# Sensor.net
KiCad netlist of a schematic drawn in Altium Designer
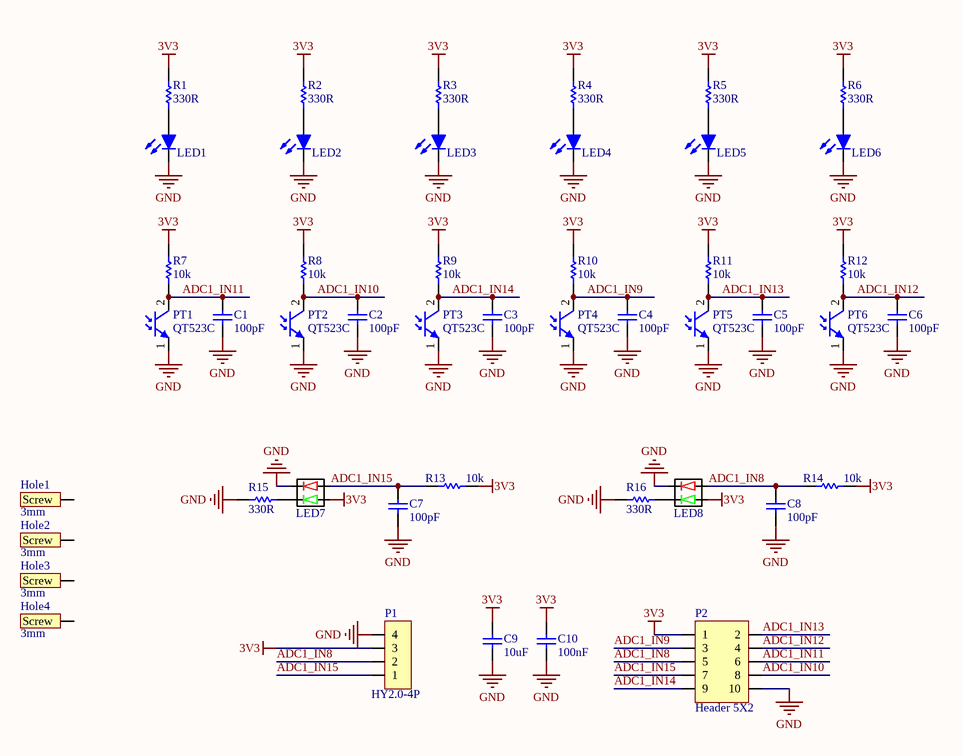
[diagram p0: Sensor.SchDoc]

(export (version "E")
  (design (tool "Eeschema 10.0.6"))
  (components
    (comp (ref "C1")
      (value "100pF")
      (footprint "C 0603 (1608)")
      (description "Capacitor non-pol")
      (libsource (lib "BKIT4U_LIB") (part "Capacitor NP"))
    )
    (comp (ref "C2")
      (value "100pF")
      (footprint "C 0603 (1608)")
      (description "Capacitor non-pol")
      (libsource (lib "BKIT4U_LIB") (part "Capacitor NP"))
    )
    (comp (ref "C3")
      (value "100pF")
      (footprint "C 0603 (1608)")
      (description "Capacitor non-pol")
      (libsource (lib "BKIT4U_LIB") (part "Capacitor NP"))
    )
    (comp (ref "C4")
      (value "100pF")
      (footprint "C 0603 (1608)")
      (description "Capacitor non-pol")
      (libsource (lib "BKIT4U_LIB") (part "Capacitor NP"))
    )
    (comp (ref "C5")
      (value "100pF")
      (footprint "C 0603 (1608)")
      (description "Capacitor non-pol")
      (libsource (lib "BKIT4U_LIB") (part "Capacitor NP"))
    )
    (comp (ref "C6")
      (value "100pF")
      (footprint "C 0603 (1608)")
      (description "Capacitor non-pol")
      (libsource (lib "BKIT4U_LIB") (part "Capacitor NP"))
    )
    (comp (ref "C7")
      (value "100pF")
      (footprint "C 0603 (1608)")
      (description "Capacitor non-pol")
      (libsource (lib "BKIT4U_LIB") (part "Capacitor NP"))
    )
    (comp (ref "C8")
      (value "100pF")
      (footprint "C 0603 (1608)")
      (description "Capacitor non-pol")
      (libsource (lib "BKIT4U_LIB") (part "Capacitor NP"))
    )
    (comp (ref "C9")
      (value "10uF")
      (footprint "C 0603 (1608)")
      (description "Capacitor non-pol")
      (libsource (lib "BKIT4U_LIB") (part "Capacitor NP"))
    )
    (comp (ref "C10")
      (value "100nF")
      (footprint "C 0603 (1608)")
      (description "Capacitor non-pol")
      (libsource (lib "BKIT4U_LIB") (part "Capacitor NP"))
    )
    (comp (ref "Hole1") (value "3mm") (footprint "SCREW/3M/7M") (libsource (lib "BKIT4U_LIB") (part "Screw")))
    (comp (ref "Hole2") (value "3mm") (footprint "SCREW/3M/7M") (libsource (lib "BKIT4U_LIB") (part "Screw")))
    (comp (ref "Hole3") (value "3mm") (footprint "SCREW/3M/7M") (libsource (lib "BKIT4U_LIB") (part "Screw")))
    (comp (ref "Hole4") (value "3mm") (footprint "SCREW/3M/7M") (libsource (lib "BKIT4U_LIB") (part "Screw")))
    (comp (ref "LED1")
      (value "Led-Red")
      (footprint "LED 5MM")
      (description "Typical LED")
      (libsource (lib "BKIT4U_LIB") (part "Led"))
    )
    (comp (ref "LED2")
      (value "Led-Red")
      (footprint "LED 5MM")
      (description "Typical LED")
      (libsource (lib "BKIT4U_LIB") (part "Led"))
    )
    (comp (ref "LED3")
      (value "Led-Red")
      (footprint "LED 5MM")
      (description "Typical LED")
      (libsource (lib "BKIT4U_LIB") (part "Led"))
    )
    (comp (ref "LED4")
      (value "Led-Red")
      (footprint "LED 5MM")
      (description "Typical LED")
      (libsource (lib "BKIT4U_LIB") (part "Led"))
    )
    (comp (ref "LED5")
      (value "Led-Red")
      (footprint "LED 5MM")
      (description "Typical LED")
      (libsource (lib "BKIT4U_LIB") (part "Led"))
    )
    (comp (ref "LED6")
      (value "Led-Red")
      (footprint "LED 5MM")
      (description "Typical LED")
      (libsource (lib "BKIT4U_LIB") (part "Led"))
    )
    (comp (ref "LED7")
      (value "LED F2/3MM 90")
      (footprint "LED 2x3MM 90")
      (description "Typical LED")
      (libsource (lib "BKIT4U_LIB") (part "LED F2/3MM 90"))
    )
    (comp (ref "LED8")
      (value "LED F2/3MM 90")
      (footprint "LED 2x3MM 90")
      (description "Typical LED")
      (libsource (lib "BKIT4U_LIB") (part "LED F2/3MM 90"))
    )
    (comp (ref "P1")
      (value "HY2.0-4P")
      (footprint "HY2.0-4P-RA")
      (description "Header, 4-Pin")
      (libsource (lib "BKIT4U_LIB") (part "Header 4"))
    )
    (comp (ref "P2")
      (value "Header 5X2")
      (footprint "DC3-10P-1.27MM")
      (description "Header, 5-Pin, Dual row")
      (fields (field (name "PUBLISHER") "Altium Limited"))
      (libsource (lib "BKIT4U_LIB") (part "Header 5X2"))
    )
    (comp (ref "PT1")
      (value "QT523C")
      (footprint "QT523C 5800B")
      (description "PHOTODIODE 5800B")
      (libsource (lib "BKIT4U_LIB") (part "QT523C"))
    )
    (comp (ref "PT2")
      (value "QT523C")
      (footprint "QT523C 5800B")
      (description "PHOTODIODE 5800B")
      (libsource (lib "BKIT4U_LIB") (part "QT523C"))
    )
    (comp (ref "PT3")
      (value "QT523C")
      (footprint "QT523C 5800B")
      (description "PHOTODIODE 5800B")
      (libsource (lib "BKIT4U_LIB") (part "QT523C"))
    )
    (comp (ref "PT4")
      (value "QT523C")
      (footprint "QT523C 5800B")
      (description "PHOTODIODE 5800B")
      (libsource (lib "BKIT4U_LIB") (part "QT523C"))
    )
    (comp (ref "PT5")
      (value "QT523C")
      (footprint "QT523C 5800B")
      (description "PHOTODIODE 5800B")
      (libsource (lib "BKIT4U_LIB") (part "QT523C"))
    )
    (comp (ref "PT6")
      (value "QT523C")
      (footprint "QT523C 5800B")
      (description "PHOTODIODE 5800B")
      (libsource (lib "BKIT4U_LIB") (part "QT523C"))
    )
    (comp (ref "R1")
      (value "330R")
      (footprint "R 0603 (1608)")
      (description "Resistor")
      (fields (field (name "PUBLISHER") "Altium Limited"))
      (libsource (lib "BKIT4U_LIB") (part "Resistor"))
    )
    (comp (ref "R2")
      (value "330R")
      (footprint "R 0603 (1608)")
      (description "Resistor")
      (fields (field (name "PUBLISHER") "Altium Limited"))
      (libsource (lib "BKIT4U_LIB") (part "Resistor"))
    )
    (comp (ref "R3")
      (value "330R")
      (footprint "R 0603 (1608)")
      (description "Resistor")
      (fields (field (name "PUBLISHER") "Altium Limited"))
      (libsource (lib "BKIT4U_LIB") (part "Resistor"))
    )
    (comp (ref "R4")
      (value "330R")
      (footprint "R 0603 (1608)")
      (description "Resistor")
      (fields (field (name "PUBLISHER") "Altium Limited"))
      (libsource (lib "BKIT4U_LIB") (part "Resistor"))
    )
    (comp (ref "R5")
      (value "330R")
      (footprint "R 0603 (1608)")
      (description "Resistor")
      (fields (field (name "PUBLISHER") "Altium Limited"))
      (libsource (lib "BKIT4U_LIB") (part "Resistor"))
    )
    (comp (ref "R6")
      (value "330R")
      (footprint "R 0603 (1608)")
      (description "Resistor")
      (fields (field (name "PUBLISHER") "Altium Limited"))
      (libsource (lib "BKIT4U_LIB") (part "Resistor"))
    )
    (comp (ref "R7")
      (value "10k")
      (footprint "R 0603 (1608)")
      (description "Resistor")
      (fields (field (name "PUBLISHER") "Altium Limited"))
      (libsource (lib "BKIT4U_LIB") (part "Resistor"))
    )
    (comp (ref "R8")
      (value "10k")
      (footprint "R 0603 (1608)")
      (description "Resistor")
      (fields (field (name "PUBLISHER") "Altium Limited"))
      (libsource (lib "BKIT4U_LIB") (part "Resistor"))
    )
    (comp (ref "R9")
      (value "10k")
      (footprint "R 0603 (1608)")
      (description "Resistor")
      (fields (field (name "PUBLISHER") "Altium Limited"))
      (libsource (lib "BKIT4U_LIB") (part "Resistor"))
    )
    (comp (ref "R10")
      (value "10k")
      (footprint "R 0603 (1608)")
      (description "Resistor")
      (fields (field (name "PUBLISHER") "Altium Limited"))
      (libsource (lib "BKIT4U_LIB") (part "Resistor"))
    )
    (comp (ref "R11")
      (value "10k")
      (footprint "R 0603 (1608)")
      (description "Resistor")
      (fields (field (name "PUBLISHER") "Altium Limited"))
      (libsource (lib "BKIT4U_LIB") (part "Resistor"))
    )
    (comp (ref "R12")
      (value "10k")
      (footprint "R 0603 (1608)")
      (description "Resistor")
      (fields (field (name "PUBLISHER") "Altium Limited"))
      (libsource (lib "BKIT4U_LIB") (part "Resistor"))
    )
    (comp (ref "R13")
      (value "10k")
      (footprint "R 0603 (1608)")
      (description "Resistor")
      (fields (field (name "PUBLISHER") "Altium Limited"))
      (libsource (lib "BKIT4U_LIB") (part "Resistor"))
    )
    (comp (ref "R14")
      (value "10k")
      (footprint "R 0603 (1608)")
      (description "Resistor")
      (fields (field (name "PUBLISHER") "Altium Limited"))
      (libsource (lib "BKIT4U_LIB") (part "Resistor"))
    )
    (comp (ref "R15")
      (value "330R")
      (footprint "R 0603 (1608)")
      (description "Resistor")
      (fields (field (name "PUBLISHER") "Altium Limited"))
      (libsource (lib "BKIT4U_LIB") (part "Resistor"))
    )
    (comp (ref "R16")
      (value "330R")
      (footprint "R 0603 (1608)")
      (description "Resistor")
      (fields (field (name "PUBLISHER") "Altium Limited"))
      (libsource (lib "BKIT4U_LIB") (part "Resistor"))
    )
  )
  (nets
    (net (code "1") (name "/ADC1_IN8") (class "Default")
      (node (ref "C8") (pin "1") (pinfunction "1_1") (pintype "passive"))
      (node (ref "LED8") (pin "1") (pinfunction "A_1") (pintype "passive"))
      (node (ref "P1") (pin "2") (pinfunction "2_2") (pintype "passive"))
      (node (ref "P2") (pin "5") (pinfunction "5_5") (pintype "passive"))
      (node (ref "R14") (pin "2") (pinfunction "2_2") (pintype "passive"))
    )
    (net (code "2") (name "/ADC1_IN9") (class "Default")
      (node (ref "C4") (pin "1") (pinfunction "1_1") (pintype "passive"))
      (node (ref "P2") (pin "3") (pinfunction "3_3") (pintype "passive"))
      (node (ref "PT4") (pin "2") (pinfunction "C_2") (pintype "passive"))
      (node (ref "R10") (pin "1") (pinfunction "1_1") (pintype "passive"))
    )
    (net (code "3") (name "/ADC1_IN10") (class "Default")
      (node (ref "C2") (pin "1") (pinfunction "1_1") (pintype "passive"))
      (node (ref "P2") (pin "8") (pinfunction "8_8") (pintype "passive"))
      (node (ref "PT2") (pin "2") (pinfunction "C_2") (pintype "passive"))
      (node (ref "R8") (pin "1") (pinfunction "1_1") (pintype "passive"))
    )
    (net (code "4") (name "/ADC1_IN11") (class "Default")
      (node (ref "C1") (pin "1") (pinfunction "1_1") (pintype "passive"))
      (node (ref "P2") (pin "6") (pinfunction "6_6") (pintype "passive"))
      (node (ref "PT1") (pin "2") (pinfunction "C_2") (pintype "passive"))
      (node (ref "R7") (pin "1") (pinfunction "1_1") (pintype "passive"))
    )
    (net (code "5") (name "/ADC1_IN12") (class "Default")
      (node (ref "C6") (pin "1") (pinfunction "1_1") (pintype "passive"))
      (node (ref "P2") (pin "4") (pinfunction "4_4") (pintype "passive"))
      (node (ref "PT6") (pin "2") (pinfunction "C_2") (pintype "passive"))
      (node (ref "R12") (pin "1") (pinfunction "1_1") (pintype "passive"))
    )
    (net (code "6") (name "/ADC1_IN13") (class "Default")
      (node (ref "C5") (pin "1") (pinfunction "1_1") (pintype "passive"))
      (node (ref "P2") (pin "2") (pinfunction "2_2") (pintype "passive"))
      (node (ref "PT5") (pin "2") (pinfunction "C_2") (pintype "passive"))
      (node (ref "R11") (pin "1") (pinfunction "1_1") (pintype "passive"))
    )
    (net (code "7") (name "/ADC1_IN14") (class "Default")
      (node (ref "C3") (pin "1") (pinfunction "1_1") (pintype "passive"))
      (node (ref "P2") (pin "9") (pinfunction "9_9") (pintype "passive"))
      (node (ref "PT3") (pin "2") (pinfunction "C_2") (pintype "passive"))
      (node (ref "R9") (pin "1") (pinfunction "1_1") (pintype "passive"))
    )
    (net (code "8") (name "/ADC1_IN15") (class "Default")
      (node (ref "C7") (pin "1") (pinfunction "1_1") (pintype "passive"))
      (node (ref "LED7") (pin "1") (pinfunction "A_1") (pintype "passive"))
      (node (ref "P1") (pin "1") (pinfunction "1_1") (pintype "passive"))
      (node (ref "P2") (pin "7") (pinfunction "7_7") (pintype "passive"))
      (node (ref "R13") (pin "2") (pinfunction "2_2") (pintype "passive"))
    )
    (net (code "9") (name "3V3") (class "Default")
      (node (ref "C10") (pin "1") (pinfunction "1_1") (pintype "passive"))
      (node (ref "C9") (pin "1") (pinfunction "1_1") (pintype "passive"))
      (node (ref "LED7") (pin "3") (pinfunction "A_3") (pintype "passive"))
      (node (ref "LED8") (pin "3") (pinfunction "A_3") (pintype "passive"))
      (node (ref "P1") (pin "3") (pinfunction "3_3") (pintype "passive"))
      (node (ref "P2") (pin "1") (pinfunction "1_1") (pintype "passive"))
      (node (ref "R1") (pin "2") (pinfunction "2_2") (pintype "passive"))
      (node (ref "R10") (pin "2") (pinfunction "2_2") (pintype "passive"))
      (node (ref "R11") (pin "2") (pinfunction "2_2") (pintype "passive"))
      (node (ref "R12") (pin "2") (pinfunction "2_2") (pintype "passive"))
      (node (ref "R13") (pin "1") (pinfunction "1_1") (pintype "passive"))
      (node (ref "R14") (pin "1") (pinfunction "1_1") (pintype "passive"))
      (node (ref "R2") (pin "2") (pinfunction "2_2") (pintype "passive"))
      (node (ref "R3") (pin "2") (pinfunction "2_2") (pintype "passive"))
      (node (ref "R4") (pin "2") (pinfunction "2_2") (pintype "passive"))
      (node (ref "R5") (pin "2") (pinfunction "2_2") (pintype "passive"))
      (node (ref "R6") (pin "2") (pinfunction "2_2") (pintype "passive"))
      (node (ref "R7") (pin "2") (pinfunction "2_2") (pintype "passive"))
      (node (ref "R8") (pin "2") (pinfunction "2_2") (pintype "passive"))
      (node (ref "R9") (pin "2") (pinfunction "2_2") (pintype "passive"))
    )
    (net (code "10") (name "GND") (class "Default")
      (node (ref "C1") (pin "2") (pinfunction "2_2") (pintype "passive"))
      (node (ref "C10") (pin "2") (pinfunction "2_2") (pintype "passive"))
      (node (ref "C2") (pin "2") (pinfunction "2_2") (pintype "passive"))
      (node (ref "C3") (pin "2") (pinfunction "2_2") (pintype "passive"))
      (node (ref "C4") (pin "2") (pinfunction "2_2") (pintype "passive"))
      (node (ref "C5") (pin "2") (pinfunction "2_2") (pintype "passive"))
      (node (ref "C6") (pin "2") (pinfunction "2_2") (pintype "passive"))
      (node (ref "C7") (pin "2") (pinfunction "2_2") (pintype "passive"))
      (node (ref "C8") (pin "2") (pinfunction "2_2") (pintype "passive"))
      (node (ref "C9") (pin "2") (pinfunction "2_2") (pintype "passive"))
      (node (ref "LED1") (pin "2") (pinfunction "K_2") (pintype "passive"))
      (node (ref "LED2") (pin "2") (pinfunction "K_2") (pintype "passive"))
      (node (ref "LED3") (pin "2") (pinfunction "K_2") (pintype "passive"))
      (node (ref "LED4") (pin "2") (pinfunction "K_2") (pintype "passive"))
      (node (ref "LED5") (pin "2") (pinfunction "K_2") (pintype "passive"))
      (node (ref "LED6") (pin "2") (pinfunction "K_2") (pintype "passive"))
      (node (ref "LED7") (pin "2") (pinfunction "K_2") (pintype "passive"))
      (node (ref "LED8") (pin "2") (pinfunction "K_2") (pintype "passive"))
      (node (ref "P1") (pin "4") (pinfunction "4_4") (pintype "passive"))
      (node (ref "P2") (pin "10") (pinfunction "10_10") (pintype "passive"))
      (node (ref "PT1") (pin "1") (pinfunction "E_1") (pintype "passive"))
      (node (ref "PT2") (pin "1") (pinfunction "E_1") (pintype "passive"))
      (node (ref "PT3") (pin "1") (pinfunction "E_1") (pintype "passive"))
      (node (ref "PT4") (pin "1") (pinfunction "E_1") (pintype "passive"))
      (node (ref "PT5") (pin "1") (pinfunction "E_1") (pintype "passive"))
      (node (ref "PT6") (pin "1") (pinfunction "E_1") (pintype "passive"))
      (node (ref "R15") (pin "2") (pinfunction "2_2") (pintype "passive"))
      (node (ref "R16") (pin "2") (pinfunction "2_2") (pintype "passive"))
    )
    (net (code "11") (name "Net-(LED1-A)") (class "Default")
      (node (ref "LED1") (pin "1") (pinfunction "A_1") (pintype "passive"))
      (node (ref "R1") (pin "1") (pinfunction "1_1") (pintype "passive"))
    )
    (net (code "12") (name "Net-(LED2-A)") (class "Default")
      (node (ref "LED2") (pin "1") (pinfunction "A_1") (pintype "passive"))
      (node (ref "R2") (pin "1") (pinfunction "1_1") (pintype "passive"))
    )
    (net (code "13") (name "Net-(LED3-A)") (class "Default")
      (node (ref "LED3") (pin "1") (pinfunction "A_1") (pintype "passive"))
      (node (ref "R3") (pin "1") (pinfunction "1_1") (pintype "passive"))
    )
    (net (code "14") (name "Net-(LED4-A)") (class "Default")
      (node (ref "LED4") (pin "1") (pinfunction "A_1") (pintype "passive"))
      (node (ref "R4") (pin "1") (pinfunction "1_1") (pintype "passive"))
    )
    (net (code "15") (name "Net-(LED5-A)") (class "Default")
      (node (ref "LED5") (pin "1") (pinfunction "A_1") (pintype "passive"))
      (node (ref "R5") (pin "1") (pinfunction "1_1") (pintype "passive"))
    )
    (net (code "16") (name "Net-(LED6-A)") (class "Default")
      (node (ref "LED6") (pin "1") (pinfunction "A_1") (pintype "passive"))
      (node (ref "R6") (pin "1") (pinfunction "1_1") (pintype "passive"))
    )
    (net (code "17") (name "Net-(LED7-K-Pad4)") (class "Default")
      (node (ref "LED7") (pin "4") (pinfunction "K_4") (pintype "passive"))
      (node (ref "R15") (pin "1") (pinfunction "1_1") (pintype "passive"))
    )
    (net (code "18") (name "Net-(LED8-K-Pad4)") (class "Default")
      (node (ref "LED8") (pin "4") (pinfunction "K_4") (pintype "passive"))
      (node (ref "R16") (pin "1") (pinfunction "1_1") (pintype "passive"))
    )
    (net (code "19") (name "unconnected-(Hole1-Screw-Pad1)") (class "Default")
      (node (ref "Hole1") (pin "1") (pinfunction "Screw_1") (pintype "passive"))
    )
    (net (code "20") (name "unconnected-(Hole2-Screw-Pad1)") (class "Default")
      (node (ref "Hole2") (pin "1") (pinfunction "Screw_1") (pintype "passive"))
    )
    (net (code "21") (name "unconnected-(Hole3-Screw-Pad1)") (class "Default")
      (node (ref "Hole3") (pin "1") (pinfunction "Screw_1") (pintype "passive"))
    )
    (net (code "22") (name "unconnected-(Hole4-Screw-Pad1)") (class "Default")
      (node (ref "Hole4") (pin "1") (pinfunction "Screw_1") (pintype "passive"))
    )
  )
)
